# led.net
KiCad netlist of a schematic drawn in Altium Designer
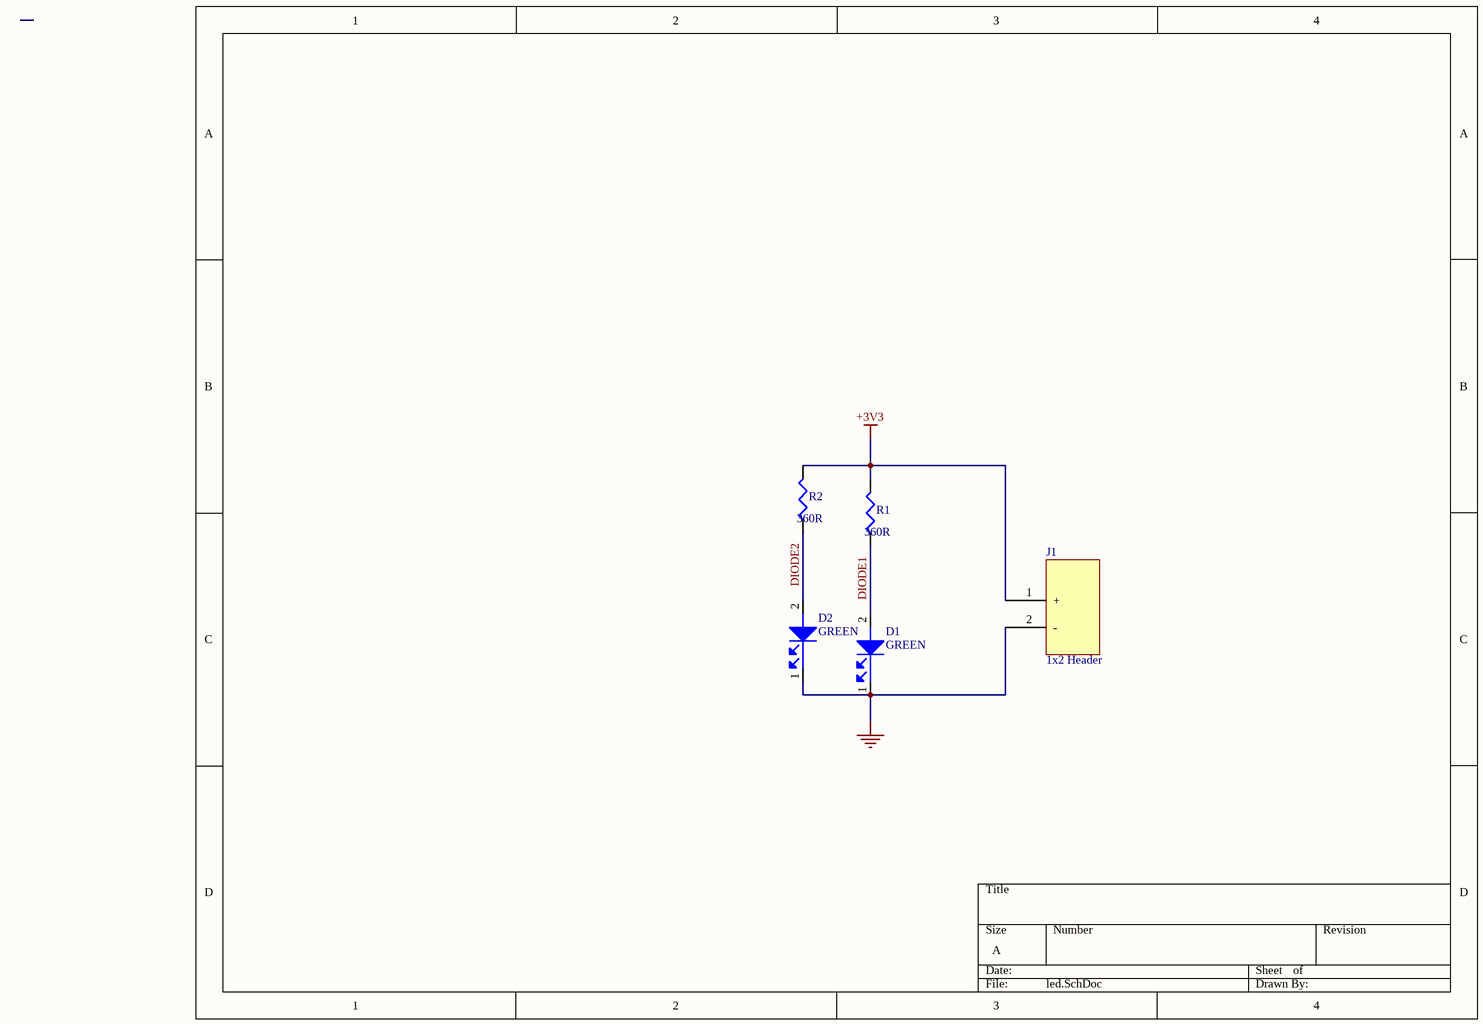
[diagram p0: led.SchDoc]

(export (version "E")
  (design (tool "Eeschema 10.0.6"))
  (components
    (comp (ref "D1")
      (value "GREEN")
      (footprint "LED0603G")
      (description "LED GREEN CLEAR CHIP 0603 SMD")
      (fields
        (field (name "MANUFACTURER") "Visual Communications")
        (field (name "MANUFACTURER PART NUMBER") "LSM0603453V")
      )
      (libsource (lib "led_Schlib") (part "LSM0603453V"))
    )
    (comp (ref "D2")
      (value "GREEN")
      (footprint "LED0603G")
      (description "LED GREEN CLEAR CHIP 0603 SMD")
      (fields
        (field (name "MANUFACTURER") "Visual Communications")
        (field (name "MANUFACTURER PART NUMBER") "LSM0603453V")
      )
      (libsource (lib "led_Schlib") (part "LSM0603453V"))
    )
    (comp (ref "J1")
      (value "1x2 Header")
      (footprint "HDR1x2")
      (description "CONN HEADER VERT 2POS 2.54MM")
      (fields (field (name "MANUFACTURER") "Molex") (field (name "MANUFACTURER PART NUMBER") "22-27-2021"))
      (libsource (lib "led_Schlib") (part "22-27-2021"))
    )
    (comp (ref "R1")
      (value "360R")
      (footprint "R0805 - duplicate")
      (description "RES SMD 360 OHM 1% 1/8W 0805")
      (fields
        (field (name "MANUFACTURER") "Yageo")
        (field (name "MANUFACTURER PART NUMBER") "AC0805FR-07360RL")
      )
      (libsource (lib "led_Schlib") (part "AC0805FR-07360RL"))
    )
    (comp (ref "R2")
      (value "360R")
      (footprint "R0805 - duplicate")
      (description "RES SMD 360 OHM 1% 1/8W 0805")
      (fields
        (field (name "MANUFACTURER") "Yageo")
        (field (name "MANUFACTURER PART NUMBER") "AC0805FR-07360RL")
      )
      (libsource (lib "led_Schlib") (part "AC0805FR-07360RL"))
    )
  )
  (nets
    (net (code "1") (name "+3V3") (class "Default")
      (node (ref "J1") (pin "1") (pinfunction "+_1") (pintype "passive"))
      (node (ref "R1") (pin "2") (pinfunction "2_2") (pintype "passive"))
      (node (ref "R2") (pin "2") (pinfunction "2_2") (pintype "passive"))
    )
    (net (code "2") (name "/DIODE1") (class "Default")
      (node (ref "D1") (pin "2") (pinfunction "2_2") (pintype "passive"))
      (node (ref "R1") (pin "1") (pinfunction "1_1") (pintype "passive"))
    )
    (net (code "3") (name "/DIODE2") (class "Default")
      (node (ref "D2") (pin "2") (pinfunction "2_2") (pintype "passive"))
      (node (ref "R2") (pin "1") (pinfunction "1_1") (pintype "passive"))
    )
    (net (code "4") (name "VCC") (class "Default")
      (node (ref "D1") (pin "1") (pinfunction "1_1") (pintype "passive"))
      (node (ref "D2") (pin "1") (pinfunction "1_1") (pintype "passive"))
      (node (ref "J1") (pin "2") (pinfunction "-_2") (pintype "passive"))
    )
  )
)
